# LAN8830_PINOUT.net
KiCad netlist of a schematic drawn in Altium Designer
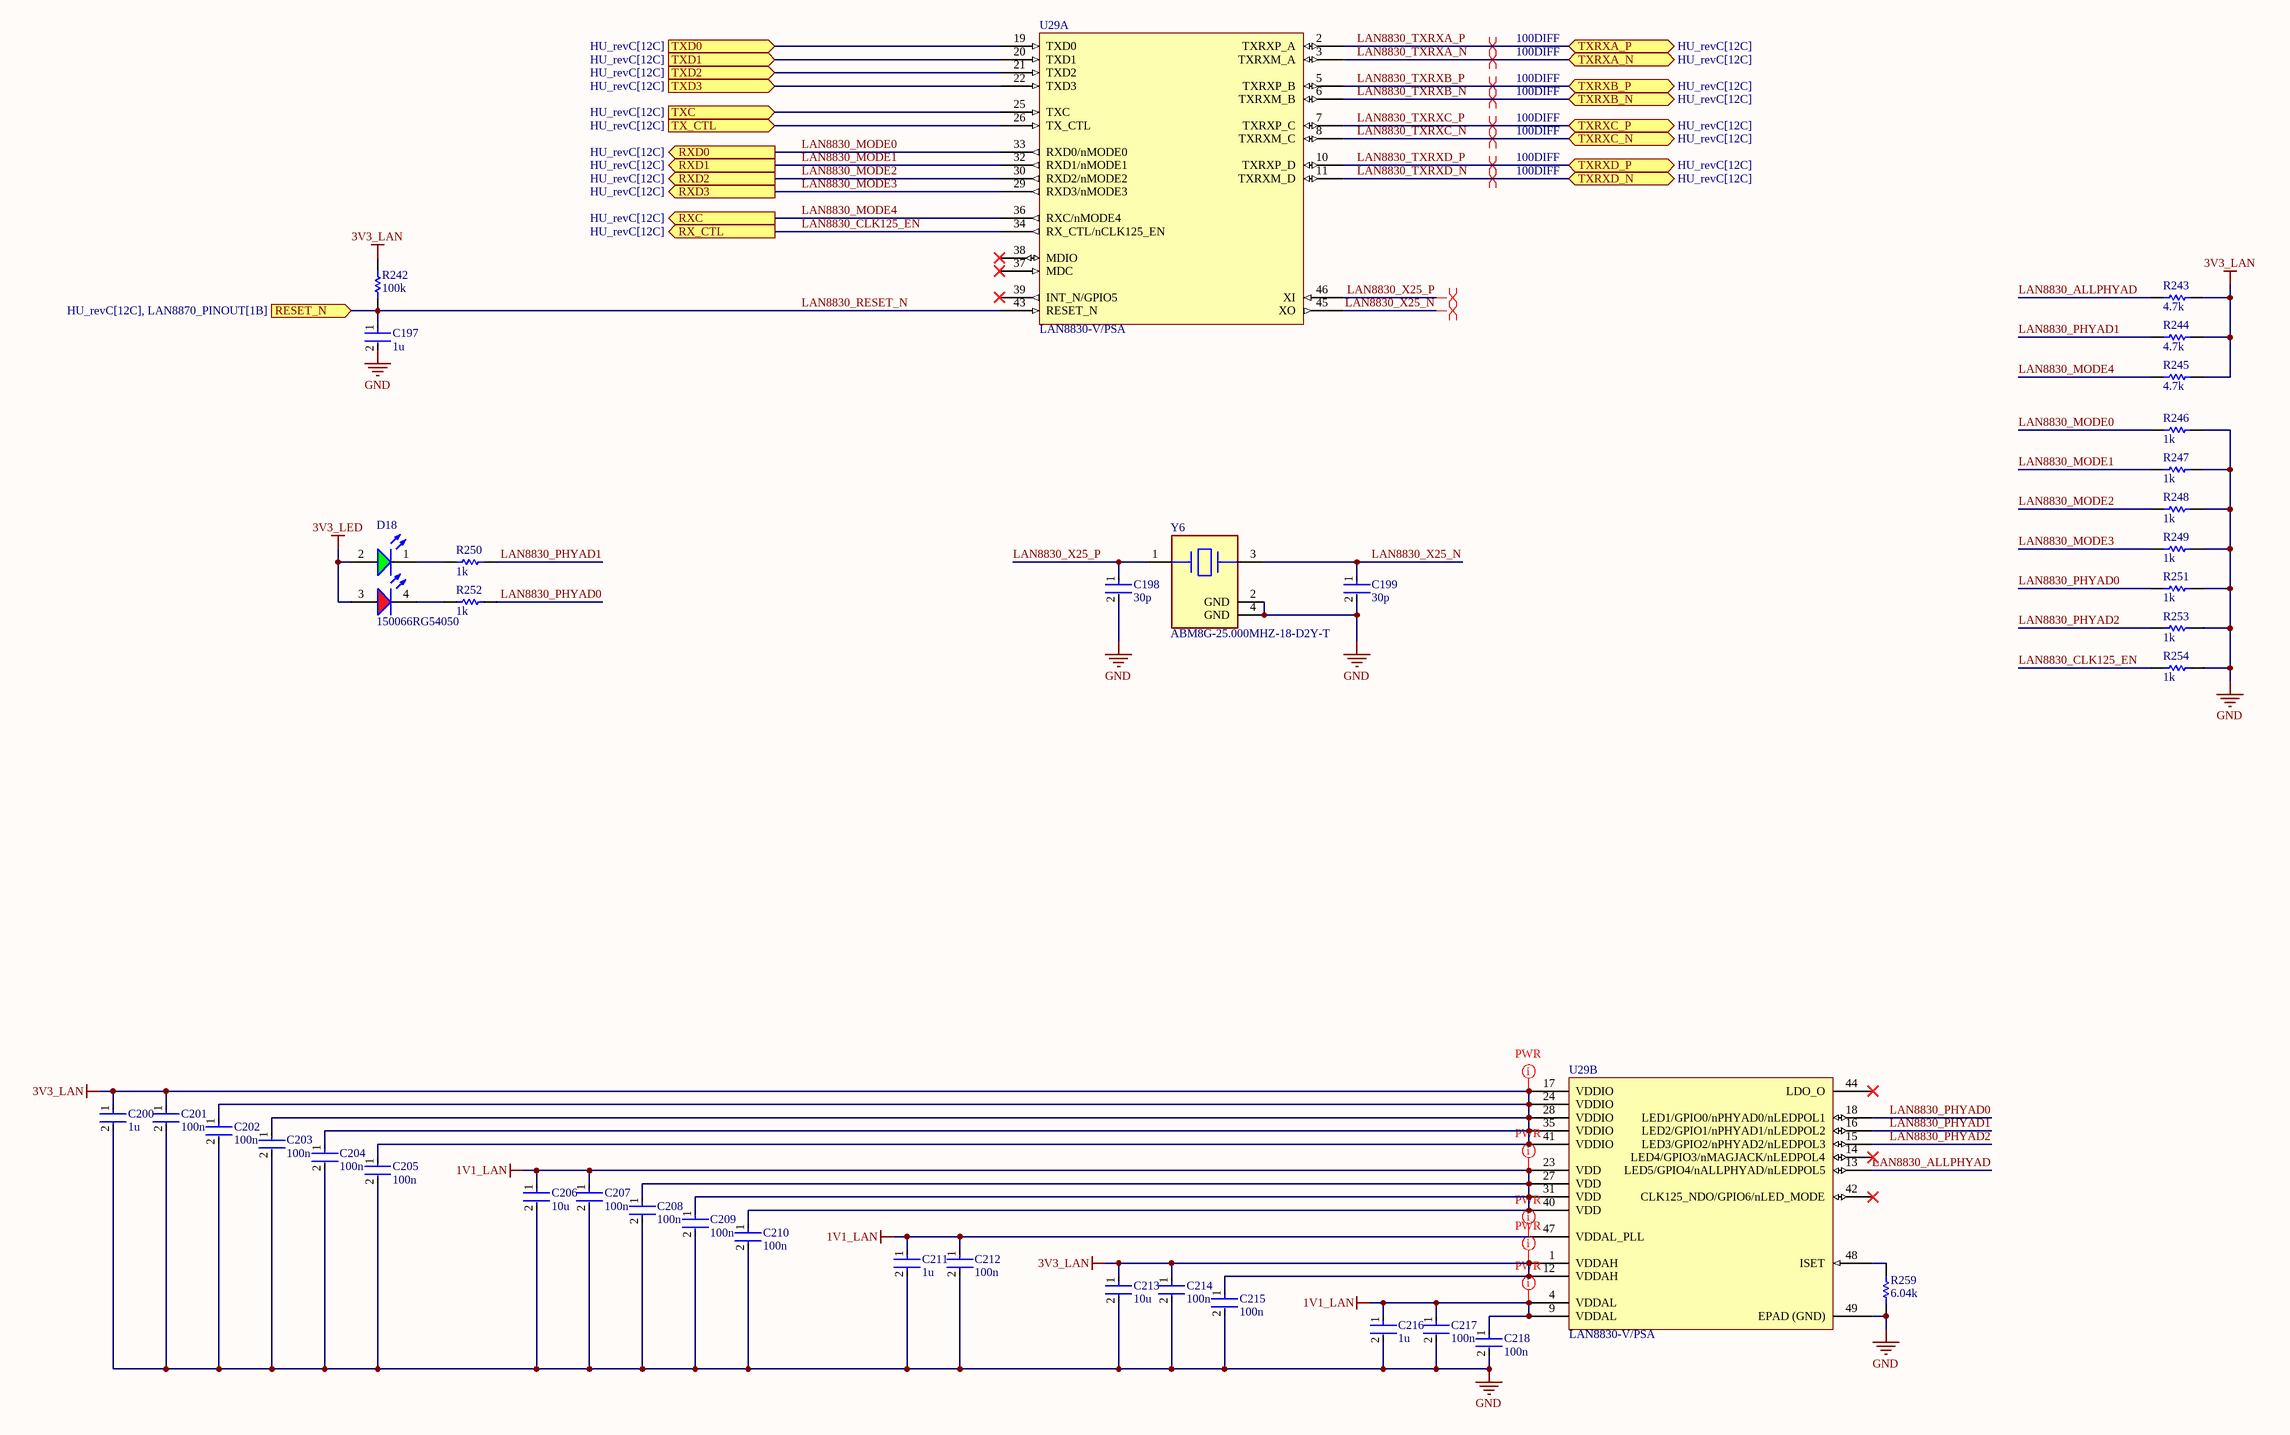
[diagram p0: LAN8830_PINOUT.SchDoc]

(export (version "E")
  (design (tool "Eeschema 10.0.6"))
  (components
    (comp (ref "C197")
      (value "1u")
      (footprint "FP-0402-L_1_0_0_05-W_0_5-IPC_A")
      (description "LARGE PADS, 0402 CAP, CHANGE COMMENT TO MATCH REAL P/N")
      (libsource (lib "Space Concordia") (part "b4654b650e69147ec39a6b967a45e02"))
    )
    (comp (ref "C198")
      (value "30p")
      (footprint "FP-0402-L_1_0_0_05-W_0_5-IPC_A")
      (description "LARGE PADS, 0402 CAP, CHANGE COMMENT TO MATCH REAL P/N")
      (libsource (lib "Space Concordia") (part "b4654b650e69147ec39a6b967a45e02"))
    )
    (comp (ref "C199")
      (value "30p")
      (footprint "FP-0402-L_1_0_0_05-W_0_5-IPC_A")
      (description "LARGE PADS, 0402 CAP, CHANGE COMMENT TO MATCH REAL P/N")
      (libsource (lib "Space Concordia") (part "b4654b650e69147ec39a6b967a45e02"))
    )
    (comp (ref "C200")
      (value "1u")
      (footprint "FP-0402-L_1_0_0_05-W_0_5-IPC_A")
      (description "LARGE PADS, 0402 CAP, CHANGE COMMENT TO MATCH REAL P/N")
      (libsource (lib "Space Concordia") (part "b4654b650e69147ec39a6b967a45e02"))
    )
    (comp (ref "C201")
      (value "100n")
      (footprint "FP-0402-L_1_0_0_05-W_0_5-IPC_A")
      (description "LARGE PADS, 0402 CAP, CHANGE COMMENT TO MATCH REAL P/N")
      (libsource (lib "Space Concordia") (part "b4654b650e69147ec39a6b967a45e02"))
    )
    (comp (ref "C202")
      (value "100n")
      (footprint "FP-0402-L_1_0_0_05-W_0_5-IPC_A")
      (description "LARGE PADS, 0402 CAP, CHANGE COMMENT TO MATCH REAL P/N")
      (libsource (lib "Space Concordia") (part "b4654b650e69147ec39a6b967a45e02"))
    )
    (comp (ref "C203")
      (value "100n")
      (footprint "FP-0402-L_1_0_0_05-W_0_5-IPC_A")
      (description "LARGE PADS, 0402 CAP, CHANGE COMMENT TO MATCH REAL P/N")
      (libsource (lib "Space Concordia") (part "b4654b650e69147ec39a6b967a45e02"))
    )
    (comp (ref "C204")
      (value "100n")
      (footprint "FP-0402-L_1_0_0_05-W_0_5-IPC_A")
      (description "LARGE PADS, 0402 CAP, CHANGE COMMENT TO MATCH REAL P/N")
      (libsource (lib "Space Concordia") (part "b4654b650e69147ec39a6b967a45e02"))
    )
    (comp (ref "C205")
      (value "100n")
      (footprint "FP-0402-L_1_0_0_05-W_0_5-IPC_A")
      (description "LARGE PADS, 0402 CAP, CHANGE COMMENT TO MATCH REAL P/N")
      (libsource (lib "Space Concordia") (part "b4654b650e69147ec39a6b967a45e02"))
    )
    (comp (ref "C206")
      (value "10u")
      (footprint "FP-0402-L_1_0_0_05-W_0_5-IPC_A")
      (description "LARGE PADS, 0402 CAP, CHANGE COMMENT TO MATCH REAL P/N")
      (libsource (lib "Space Concordia") (part "b4654b650e69147ec39a6b967a45e02"))
    )
    (comp (ref "C207")
      (value "100n")
      (footprint "FP-0402-L_1_0_0_05-W_0_5-IPC_A")
      (description "LARGE PADS, 0402 CAP, CHANGE COMMENT TO MATCH REAL P/N")
      (libsource (lib "Space Concordia") (part "b4654b650e69147ec39a6b967a45e02"))
    )
    (comp (ref "C208")
      (value "100n")
      (footprint "FP-0402-L_1_0_0_05-W_0_5-IPC_A")
      (description "LARGE PADS, 0402 CAP, CHANGE COMMENT TO MATCH REAL P/N")
      (libsource (lib "Space Concordia") (part "b4654b650e69147ec39a6b967a45e02"))
    )
    (comp (ref "C209")
      (value "100n")
      (footprint "FP-0402-L_1_0_0_05-W_0_5-IPC_A")
      (description "LARGE PADS, 0402 CAP, CHANGE COMMENT TO MATCH REAL P/N")
      (libsource (lib "Space Concordia") (part "b4654b650e69147ec39a6b967a45e02"))
    )
    (comp (ref "C210")
      (value "100n")
      (footprint "FP-0402-L_1_0_0_05-W_0_5-IPC_A")
      (description "LARGE PADS, 0402 CAP, CHANGE COMMENT TO MATCH REAL P/N")
      (libsource (lib "Space Concordia") (part "b4654b650e69147ec39a6b967a45e02"))
    )
    (comp (ref "C211")
      (value "1u")
      (footprint "FP-0402-L_1_0_0_05-W_0_5-IPC_A")
      (description "LARGE PADS, 0402 CAP, CHANGE COMMENT TO MATCH REAL P/N")
      (libsource (lib "Space Concordia") (part "b4654b650e69147ec39a6b967a45e02"))
    )
    (comp (ref "C212")
      (value "100n")
      (footprint "FP-0402-L_1_0_0_05-W_0_5-IPC_A")
      (description "LARGE PADS, 0402 CAP, CHANGE COMMENT TO MATCH REAL P/N")
      (libsource (lib "Space Concordia") (part "b4654b650e69147ec39a6b967a45e02"))
    )
    (comp (ref "C213")
      (value "10u")
      (footprint "FP-0402-L_1_0_0_05-W_0_5-IPC_A")
      (description "LARGE PADS, 0402 CAP, CHANGE COMMENT TO MATCH REAL P/N")
      (libsource (lib "Space Concordia") (part "b4654b650e69147ec39a6b967a45e02"))
    )
    (comp (ref "C214")
      (value "100n")
      (footprint "FP-0402-L_1_0_0_05-W_0_5-IPC_A")
      (description "LARGE PADS, 0402 CAP, CHANGE COMMENT TO MATCH REAL P/N")
      (libsource (lib "Space Concordia") (part "b4654b650e69147ec39a6b967a45e02"))
    )
    (comp (ref "C215")
      (value "100n")
      (footprint "FP-0402-L_1_0_0_05-W_0_5-IPC_A")
      (description "LARGE PADS, 0402 CAP, CHANGE COMMENT TO MATCH REAL P/N")
      (libsource (lib "Space Concordia") (part "b4654b650e69147ec39a6b967a45e02"))
    )
    (comp (ref "C216")
      (value "1u")
      (footprint "FP-0402-L_1_0_0_05-W_0_5-IPC_A")
      (description "LARGE PADS, 0402 CAP, CHANGE COMMENT TO MATCH REAL P/N")
      (libsource (lib "Space Concordia") (part "b4654b650e69147ec39a6b967a45e02"))
    )
    (comp (ref "C217")
      (value "100n")
      (footprint "FP-0402-L_1_0_0_05-W_0_5-IPC_A")
      (description "LARGE PADS, 0402 CAP, CHANGE COMMENT TO MATCH REAL P/N")
      (libsource (lib "Space Concordia") (part "b4654b650e69147ec39a6b967a45e02"))
    )
    (comp (ref "C218")
      (value "100n")
      (footprint "FP-0402-L_1_0_0_05-W_0_5-IPC_A")
      (description "LARGE PADS, 0402 CAP, CHANGE COMMENT TO MATCH REAL P/N")
      (libsource (lib "Space Concordia") (part "b4654b650e69147ec39a6b967a45e02"))
    )
    (comp (ref "D18")
      (value "150066RG54050")
      (footprint "WL-SBCD_0606")
      (description "Led, Red/Grn, 180Mcd/230Mcd, 624Nm/525Nm Rohs Compliant: Yes")
      (fields (field (name "SOURCE") "rgled.SchLib"))
      (libsource (lib "Space Concordia") (part "CMP-004-00034-2"))
    )
    (comp (ref "R242")
      (value "100k")
      (footprint "R0603B")
      (description "Resistor")
      (libsource (lib "Space Concordia") (part "Resistor"))
    )
    (comp (ref "R243")
      (value "4.7k")
      (footprint "R0603B")
      (description "Resistor")
      (libsource (lib "Space Concordia") (part "Resistor"))
    )
    (comp (ref "R244")
      (value "4.7k")
      (footprint "R0603B")
      (description "Resistor")
      (libsource (lib "Space Concordia") (part "Resistor"))
    )
    (comp (ref "R245")
      (value "4.7k")
      (footprint "R0603B")
      (description "Resistor")
      (libsource (lib "Space Concordia") (part "Resistor"))
    )
    (comp (ref "R246")
      (value "1k")
      (footprint "R0603B")
      (description "Resistor")
      (libsource (lib "Space Concordia") (part "Resistor"))
    )
    (comp (ref "R247")
      (value "1k")
      (footprint "R0603B")
      (description "Resistor")
      (libsource (lib "Space Concordia") (part "Resistor"))
    )
    (comp (ref "R248")
      (value "1k")
      (footprint "R0603B")
      (description "Resistor")
      (libsource (lib "Space Concordia") (part "Resistor"))
    )
    (comp (ref "R249")
      (value "1k")
      (footprint "R0603B")
      (description "Resistor")
      (libsource (lib "Space Concordia") (part "Resistor"))
    )
    (comp (ref "R250")
      (value "1k")
      (footprint "R0603B")
      (description "Resistor")
      (libsource (lib "Space Concordia") (part "Resistor"))
    )
    (comp (ref "R251")
      (value "1k")
      (footprint "R0603B")
      (description "Resistor")
      (libsource (lib "Space Concordia") (part "Resistor"))
    )
    (comp (ref "R252")
      (value "1k")
      (footprint "R0603B")
      (description "Resistor")
      (libsource (lib "Space Concordia") (part "Resistor"))
    )
    (comp (ref "R253")
      (value "1k")
      (footprint "R0603B")
      (description "Resistor")
      (libsource (lib "Space Concordia") (part "Resistor"))
    )
    (comp (ref "R254")
      (value "1k")
      (footprint "R0603B")
      (description "Resistor")
      (libsource (lib "Space Concordia") (part "Resistor"))
    )
    (comp (ref "R259")
      (value "6.04k")
      (footprint "R0603B")
      (description "Resistor")
      (libsource (lib "Space Concordia") (part "Resistor"))
    )
    (comp (ref "U29")
      (value "LAN8830-V/PSA")
      (footprint "QFN50P700X700X100_HS-49N")
      (description "LAN8830 Series RGMII Interface Gigabit Ethernet Transceiver - VQFN-48")
      (libsource (lib "Space Concordia") (part "LAN8830-V_PSA"))
    )
    (comp (ref "Y6")
      (value "ABM8G-25.000MHZ-18-D2Y-T")
      (footprint "FP-ABM8G-MFG")
      (description "Crystal 25MHz ±20ppm (Tol) ±30ppm (Stability) 18pF FUND 60Ω 4-Pin SMD T/R")
      (fields (field (name "TOLERANCE") "20ppm"))
      (libsource (lib "Altium Content Vault") (part "48e526d86b7f2615d98721063c72f49"))
    )
  )
  (nets
    (net (code "1") (name "/LAN8830_ALLPHYAD") (class "Default")
      (node (ref "R243") (pin "2") (pinfunction "2_2") (pintype "passive"))
      (node (ref "U29") (pin "13") (pinfunction "LED5/GPIO4/nALLPHYAD/nLEDPOL5_13") (pintype "bidirectional"))
    )
    (net (code "2") (name "/LAN8830_CLK125_EN") (class "Default")
      (node (ref "R254") (pin "2") (pinfunction "2_2") (pintype "passive"))
      (node (ref "U29") (pin "34") (pinfunction "RX_CTL/nCLK125_EN_34") (pintype "output"))
    )
    (net (code "3") (name "/LAN8830_MODE0") (class "Default")
      (node (ref "R246") (pin "2") (pinfunction "2_2") (pintype "passive"))
      (node (ref "U29") (pin "33") (pinfunction "RXD0/nMODE0_33") (pintype "output"))
    )
    (net (code "4") (name "/LAN8830_MODE1") (class "Default")
      (node (ref "R247") (pin "2") (pinfunction "2_2") (pintype "passive"))
      (node (ref "U29") (pin "32") (pinfunction "RXD1/nMODE1_32") (pintype "output"))
    )
    (net (code "5") (name "/LAN8830_MODE2") (class "Default")
      (node (ref "R248") (pin "2") (pinfunction "2_2") (pintype "passive"))
      (node (ref "U29") (pin "30") (pinfunction "RXD2/nMODE2_30") (pintype "output"))
    )
    (net (code "6") (name "/LAN8830_MODE3") (class "Default")
      (node (ref "R249") (pin "2") (pinfunction "2_2") (pintype "passive"))
      (node (ref "U29") (pin "29") (pinfunction "RXD3/nMODE3_29") (pintype "output"))
    )
    (net (code "7") (name "/LAN8830_MODE4") (class "Default")
      (node (ref "R245") (pin "2") (pinfunction "2_2") (pintype "passive"))
      (node (ref "U29") (pin "36") (pinfunction "RXC/nMODE4_36") (pintype "output"))
    )
    (net (code "8") (name "/LAN8830_PHYAD0") (class "Default")
      (node (ref "R251") (pin "2") (pinfunction "2_2") (pintype "passive"))
      (node (ref "R252") (pin "2") (pinfunction "2_2") (pintype "passive"))
      (node (ref "U29") (pin "18") (pinfunction "LED1/GPIO0/nPHYAD0/nLEDPOL1_18") (pintype "bidirectional"))
    )
    (net (code "9") (name "/LAN8830_PHYAD1") (class "Default")
      (node (ref "R244") (pin "2") (pinfunction "2_2") (pintype "passive"))
      (node (ref "R250") (pin "2") (pinfunction "2_2") (pintype "passive"))
      (node (ref "U29") (pin "16") (pinfunction "LED2/GPIO1/nPHYAD1/nLEDPOL2_16") (pintype "bidirectional"))
    )
    (net (code "10") (name "/LAN8830_PHYAD2") (class "Default")
      (node (ref "R253") (pin "2") (pinfunction "2_2") (pintype "passive"))
      (node (ref "U29") (pin "15") (pinfunction "LED3/GPIO2/nPHYAD2/nLEDPOL3_15") (pintype "bidirectional"))
    )
    (net (code "11") (name "/LAN8830_RESET_N") (class "Default")
      (node (ref "C197") (pin "1") (pinfunction "1_1") (pintype "passive"))
      (node (ref "R242") (pin "2") (pinfunction "2_2") (pintype "passive"))
      (node (ref "U29") (pin "43") (pinfunction "RESET_N_43") (pintype "input"))
    )
    (net (code "12") (name "/LAN8830_TXRXA_N") (class "Default")
      (node (ref "U29") (pin "3") (pinfunction "TXRXM_A_3") (pintype "bidirectional"))
    )
    (net (code "13") (name "/LAN8830_TXRXA_P") (class "Default")
      (node (ref "U29") (pin "2") (pinfunction "TXRXP_A_2") (pintype "bidirectional"))
    )
    (net (code "14") (name "/LAN8830_TXRXB_N") (class "Default")
      (node (ref "U29") (pin "6") (pinfunction "TXRXM_B_6") (pintype "bidirectional"))
    )
    (net (code "15") (name "/LAN8830_TXRXB_P") (class "Default")
      (node (ref "U29") (pin "5") (pinfunction "TXRXP_B_5") (pintype "bidirectional"))
    )
    (net (code "16") (name "/LAN8830_TXRXC_N") (class "Default")
      (node (ref "U29") (pin "8") (pinfunction "TXRXM_C_8") (pintype "bidirectional"))
    )
    (net (code "17") (name "/LAN8830_TXRXC_P") (class "Default")
      (node (ref "U29") (pin "7") (pinfunction "TXRXP_C_7") (pintype "bidirectional"))
    )
    (net (code "18") (name "/LAN8830_TXRXD_N") (class "Default")
      (node (ref "U29") (pin "11") (pinfunction "TXRXM_D_11") (pintype "bidirectional"))
    )
    (net (code "19") (name "/LAN8830_TXRXD_P") (class "Default")
      (node (ref "U29") (pin "10") (pinfunction "TXRXP_D_10") (pintype "bidirectional"))
    )
    (net (code "20") (name "/LAN8830_X25_N") (class "Default")
      (node (ref "C199") (pin "1") (pinfunction "1_1") (pintype "passive"))
      (node (ref "U29") (pin "45") (pinfunction "XO_45") (pintype "output"))
      (node (ref "Y6") (pin "3") (pinfunction "3_3") (pintype "passive"))
    )
    (net (code "21") (name "/LAN8830_X25_P") (class "Default")
      (node (ref "C198") (pin "1") (pinfunction "1_1") (pintype "passive"))
      (node (ref "U29") (pin "46") (pinfunction "XI_46") (pintype "input"))
      (node (ref "Y6") (pin "1") (pinfunction "1_1") (pintype "passive"))
    )
    (net (code "22") (name "/TXC") (class "Default")
      (node (ref "U29") (pin "25") (pinfunction "TXC_25") (pintype "input"))
    )
    (net (code "23") (name "/TXD0") (class "Default")
      (node (ref "U29") (pin "19") (pinfunction "TXD0_19") (pintype "input"))
    )
    (net (code "24") (name "/TXD1") (class "Default")
      (node (ref "U29") (pin "20") (pinfunction "TXD1_20") (pintype "input"))
    )
    (net (code "25") (name "/TXD2") (class "Default")
      (node (ref "U29") (pin "21") (pinfunction "TXD2_21") (pintype "input"))
    )
    (net (code "26") (name "/TXD3") (class "Default")
      (node (ref "U29") (pin "22") (pinfunction "TXD3_22") (pintype "input"))
    )
    (net (code "27") (name "/TX_CTL") (class "Default")
      (node (ref "U29") (pin "26") (pinfunction "TX_CTL_26") (pintype "input"))
    )
    (net (code "28") (name "1V1_LAN") (class "Default")
      (node (ref "C206") (pin "1") (pinfunction "1_1") (pintype "passive"))
      (node (ref "C207") (pin "1") (pinfunction "1_1") (pintype "passive"))
      (node (ref "C208") (pin "1") (pinfunction "1_1") (pintype "passive"))
      (node (ref "C209") (pin "1") (pinfunction "1_1") (pintype "passive"))
      (node (ref "C210") (pin "1") (pinfunction "1_1") (pintype "passive"))
      (node (ref "C211") (pin "1") (pinfunction "1_1") (pintype "passive"))
      (node (ref "C212") (pin "1") (pinfunction "1_1") (pintype "passive"))
      (node (ref "C216") (pin "1") (pinfunction "1_1") (pintype "passive"))
      (node (ref "C217") (pin "1") (pinfunction "1_1") (pintype "passive"))
      (node (ref "C218") (pin "1") (pinfunction "1_1") (pintype "passive"))
      (node (ref "U29") (pin "23") (pinfunction "VDD_23") (pintype "power_in"))
      (node (ref "U29") (pin "27") (pinfunction "VDD_27") (pintype "power_in"))
      (node (ref "U29") (pin "31") (pinfunction "VDD_31") (pintype "power_in"))
      (node (ref "U29") (pin "4") (pinfunction "VDDAL_4") (pintype "power_in"))
      (node (ref "U29") (pin "40") (pinfunction "VDD_40") (pintype "power_in"))
      (node (ref "U29") (pin "47") (pinfunction "VDDAL_PLL_47") (pintype "power_in"))
      (node (ref "U29") (pin "9") (pinfunction "VDDAL_9") (pintype "power_in"))
    )
    (net (code "29") (name "3V3_LAN") (class "Default")
      (node (ref "C200") (pin "1") (pinfunction "1_1") (pintype "passive"))
      (node (ref "C201") (pin "1") (pinfunction "1_1") (pintype "passive"))
      (node (ref "C202") (pin "1") (pinfunction "1_1") (pintype "passive"))
      (node (ref "C203") (pin "1") (pinfunction "1_1") (pintype "passive"))
      (node (ref "C204") (pin "1") (pinfunction "1_1") (pintype "passive"))
      (node (ref "C205") (pin "1") (pinfunction "1_1") (pintype "passive"))
      (node (ref "C213") (pin "1") (pinfunction "1_1") (pintype "passive"))
      (node (ref "C214") (pin "1") (pinfunction "1_1") (pintype "passive"))
      (node (ref "C215") (pin "1") (pinfunction "1_1") (pintype "passive"))
      (node (ref "R242") (pin "1") (pinfunction "1_1") (pintype "passive"))
      (node (ref "R243") (pin "1") (pinfunction "1_1") (pintype "passive"))
      (node (ref "R244") (pin "1") (pinfunction "1_1") (pintype "passive"))
      (node (ref "R245") (pin "1") (pinfunction "1_1") (pintype "passive"))
      (node (ref "U29") (pin "1") (pinfunction "VDDAH_1") (pintype "power_in"))
      (node (ref "U29") (pin "12") (pinfunction "VDDAH_12") (pintype "power_in"))
      (node (ref "U29") (pin "17") (pinfunction "VDDIO_17") (pintype "power_in"))
      (node (ref "U29") (pin "24") (pinfunction "VDDIO_24") (pintype "power_in"))
      (node (ref "U29") (pin "28") (pinfunction "VDDIO_28") (pintype "power_in"))
      (node (ref "U29") (pin "35") (pinfunction "VDDIO_35") (pintype "power_in"))
      (node (ref "U29") (pin "41") (pinfunction "VDDIO_41") (pintype "power_in"))
    )
    (net (code "30") (name "3V3_LED") (class "Default")
      (node (ref "D18") (pin "2") (pinfunction "A_2") (pintype "passive"))
      (node (ref "D18") (pin "3") (pinfunction "A_3") (pintype "passive"))
    )
    (net (code "31") (name "GND") (class "Default")
      (node (ref "C197") (pin "2") (pinfunction "2_2") (pintype "passive"))
      (node (ref "C198") (pin "2") (pinfunction "2_2") (pintype "passive"))
      (node (ref "C199") (pin "2") (pinfunction "2_2") (pintype "passive"))
      (node (ref "C200") (pin "2") (pinfunction "2_2") (pintype "passive"))
      (node (ref "C201") (pin "2") (pinfunction "2_2") (pintype "passive"))
      (node (ref "C202") (pin "2") (pinfunction "2_2") (pintype "passive"))
      (node (ref "C203") (pin "2") (pinfunction "2_2") (pintype "passive"))
      (node (ref "C204") (pin "2") (pinfunction "2_2") (pintype "passive"))
      (node (ref "C205") (pin "2") (pinfunction "2_2") (pintype "passive"))
      (node (ref "C206") (pin "2") (pinfunction "2_2") (pintype "passive"))
      (node (ref "C207") (pin "2") (pinfunction "2_2") (pintype "passive"))
      (node (ref "C208") (pin "2") (pinfunction "2_2") (pintype "passive"))
      (node (ref "C209") (pin "2") (pinfunction "2_2") (pintype "passive"))
      (node (ref "C210") (pin "2") (pinfunction "2_2") (pintype "passive"))
      (node (ref "C211") (pin "2") (pinfunction "2_2") (pintype "passive"))
      (node (ref "C212") (pin "2") (pinfunction "2_2") (pintype "passive"))
      (node (ref "C213") (pin "2") (pinfunction "2_2") (pintype "passive"))
      (node (ref "C214") (pin "2") (pinfunction "2_2") (pintype "passive"))
      (node (ref "C215") (pin "2") (pinfunction "2_2") (pintype "passive"))
      (node (ref "C216") (pin "2") (pinfunction "2_2") (pintype "passive"))
      (node (ref "C217") (pin "2") (pinfunction "2_2") (pintype "passive"))
      (node (ref "C218") (pin "2") (pinfunction "2_2") (pintype "passive"))
      (node (ref "R246") (pin "1") (pinfunction "1_1") (pintype "passive"))
      (node (ref "R247") (pin "1") (pinfunction "1_1") (pintype "passive"))
      (node (ref "R248") (pin "1") (pinfunction "1_1") (pintype "passive"))
      (node (ref "R249") (pin "1") (pinfunction "1_1") (pintype "passive"))
      (node (ref "R251") (pin "1") (pinfunction "1_1") (pintype "passive"))
      (node (ref "R253") (pin "1") (pinfunction "1_1") (pintype "passive"))
      (node (ref "R254") (pin "1") (pinfunction "1_1") (pintype "passive"))
      (node (ref "R259") (pin "2") (pinfunction "2_2") (pintype "passive"))
      (node (ref "U29") (pin "49") (pinfunction "EPAD_(GND)_49") (pintype "power_in"))
      (node (ref "Y6") (pin "2") (pinfunction "GND_2") (pintype "power_in"))
      (node (ref "Y6") (pin "4") (pinfunction "GND_4") (pintype "power_in"))
    )
    (net (code "32") (name "Net-(D18-K-Pad1)") (class "Default")
      (node (ref "D18") (pin "1") (pinfunction "K_1") (pintype "passive"))
      (node (ref "R250") (pin "1") (pinfunction "1_1") (pintype "passive"))
    )
    (net (code "33") (name "Net-(D18-K-Pad4)") (class "Default")
      (node (ref "D18") (pin "4") (pinfunction "K_4") (pintype "passive"))
      (node (ref "R252") (pin "1") (pinfunction "1_1") (pintype "passive"))
    )
    (net (code "34") (name "Net-(U29B-ISET)") (class "Default")
      (node (ref "R259") (pin "1") (pinfunction "1_1") (pintype "passive"))
      (node (ref "U29") (pin "48") (pinfunction "ISET_48") (pintype "input"))
    )
    (net (code "35") (name "unconnected-(U29A-INT_N{slash}GPIO5-Pad39)") (class "Default")
      (node (ref "U29") (pin "39") (pinfunction "INT_N/GPIO5_39") (pintype "output+no_connect"))
    )
    (net (code "36") (name "unconnected-(U29A-MDC-Pad37)") (class "Default")
      (node (ref "U29") (pin "37") (pinfunction "MDC_37") (pintype "input+no_connect"))
    )
    (net (code "37") (name "unconnected-(U29A-MDIO-Pad38)") (class "Default")
      (node (ref "U29") (pin "38") (pinfunction "MDIO_38") (pintype "bidirectional+no_connect"))
    )
    (net (code "38") (name "unconnected-(U29B-CLK125_NDO{slash}GPIO6{slash}nLED_MODE-Pad42)") (class "Default")
      (node (ref "U29") (pin "42") (pinfunction "CLK125_NDO/GPIO6/nLED_MODE_42") (pintype "bidirectional+no_connect"))
    )
    (net (code "39") (name "unconnected-(U29B-LDO_O-Pad44)") (class "Default")
      (node (ref "U29") (pin "44") (pinfunction "LDO_O_44") (pintype "power_in+no_connect"))
    )
    (net (code "40") (name "unconnected-(U29B-LED4{slash}GPIO3{slash}nMAGJACK{slash}nLEDPOL4-Pad14)") (class "Default")
      (node (ref "U29") (pin "14") (pinfunction "LED4/GPIO3/nMAGJACK/nLEDPOL4_14") (pintype "bidirectional+no_connect"))
    )
  )
)
